# tft_jig.net
KiCad netlist of a schematic drawn in EAGLE
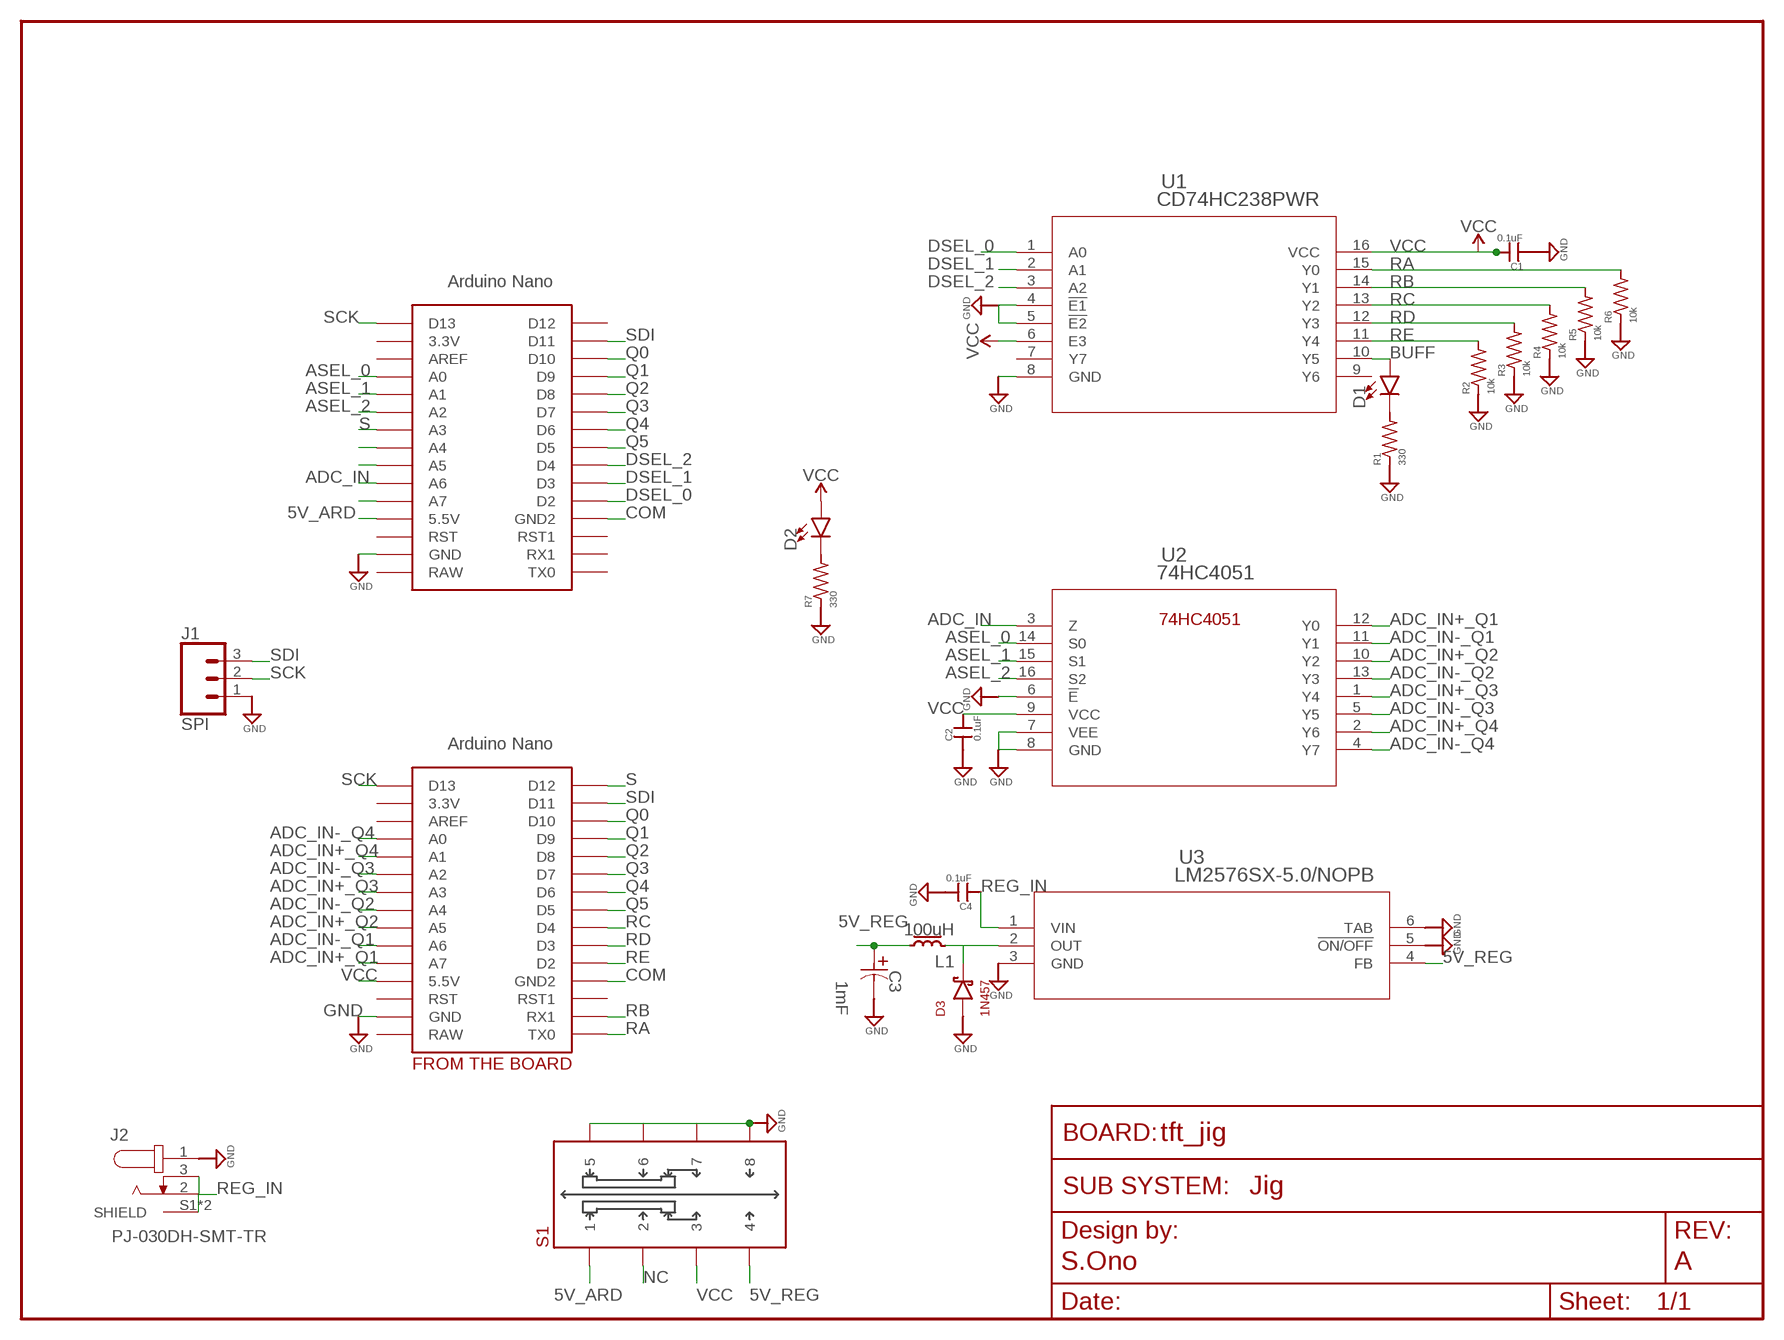
[diagram p0: schematic, sheet 1]

(export (version "E")
  (design (tool "Eeschema 10.0.6"))
  (components
    (comp (ref "C1")
      (value "0.1uF")
      (footprint "eagle-import:0603-CAP")
      (libsource (lib "eagle-import") (part "CAP0603-CAP"))
    )
    (comp (ref "C2")
      (value "0.1uF")
      (footprint "eagle-import:0603-CAP")
      (libsource (lib "eagle-import") (part "CAP0603-CAP"))
    )
    (comp (ref "C3")
      (value "1mF")
      (footprint "eagle-import:PCAP_8X10-ELECT")
      (fields (field (name "MANUFACTURER_PART_NUMBER") "UWT0J102MNL1GS"))
      (libsource (lib "eagle-import") (part "UWT0J102MNL1GS"))
    )
    (comp (ref "C4")
      (value "0.1uF")
      (footprint "eagle-import:0603-CAP")
      (libsource (lib "eagle-import") (part "CAP0603-CAP"))
    )
    (comp (ref "D1")
      (value "LED0603")
      (footprint "eagle-import:LED-0603")
      (libsource (lib "eagle-import") (part "LED0603"))
    )
    (comp (ref "D2")
      (value "LED0603")
      (footprint "eagle-import:LED-0603")
      (libsource (lib "eagle-import") (part "LED0603"))
    )
    (comp (ref "D3")
      (value "1N457")
      (footprint "eagle-import:DIODE_THRU")
      (libsource (lib "eagle-import") (part "1N457"))
    )
    (comp (ref "J1")
      (value "SPI")
      (footprint "eagle-import:1X03")
      (libsource (lib "eagle-import") (part "CONN_03"))
    )
    (comp (ref "J2")
      (value "PJ-030DH-SMT-TR")
      (footprint "eagle-import:CUI_PJ-030DH-SMT-TR")
      (fields (field (name "DIGI-KEY_PART_NUMBER") "CP-030DHPJ-CT-ND") (field (name "MF") "CUI Inc."))
      (libsource (lib "eagle-import") (part "PJ-030DH-SMT-TR"))
    )
    (comp (ref "L1")
      (value "100uH")
      (footprint "eagle-import:IND_2012")
      (fields (field (name "MANUFACTURER_PART_NUMBER") "MLZ2012M1R0HT000"))
      (libsource (lib "eagle-import") (part "IND"))
    )
    (comp (ref "R1")
      (value "330")
      (footprint "eagle-import:R0603")
      (fields (field (name "MANUFACTURER") "Rohm Semiconductor"))
      (libsource (lib "eagle-import") (part "R-US_R0603"))
    )
    (comp (ref "R2")
      (value "10k")
      (footprint "eagle-import:R0603")
      (fields (field (name "MANUFACTURER") "Rohm Semiconductor"))
      (libsource (lib "eagle-import") (part "R-US_R0603"))
    )
    (comp (ref "R3")
      (value "10k")
      (footprint "eagle-import:R0603")
      (fields (field (name "MANUFACTURER") "Rohm Semiconductor"))
      (libsource (lib "eagle-import") (part "R-US_R0603"))
    )
    (comp (ref "R4")
      (value "10k")
      (footprint "eagle-import:R0603")
      (fields (field (name "MANUFACTURER") "Rohm Semiconductor"))
      (libsource (lib "eagle-import") (part "R-US_R0603"))
    )
    (comp (ref "R5")
      (value "10k")
      (footprint "eagle-import:R0603")
      (fields (field (name "MANUFACTURER") "Rohm Semiconductor"))
      (libsource (lib "eagle-import") (part "R-US_R0603"))
    )
    (comp (ref "R6")
      (value "10k")
      (footprint "eagle-import:R0603")
      (fields (field (name "MANUFACTURER") "Rohm Semiconductor"))
      (libsource (lib "eagle-import") (part "R-US_R0603"))
    )
    (comp (ref "R7")
      (value "330")
      (footprint "eagle-import:R0603")
      (fields (field (name "MANUFACTURER") "Rohm Semiconductor"))
      (libsource (lib "eagle-import") (part "R-US_R0603"))
    )
    (comp (ref "S1")
      (value "DP3T")
      (footprint "eagle-import:DP3T")
      (libsource (lib "eagle-import") (part "DP3T"))
    )
    (comp (ref "U$1")
      (value "NANO")
      (footprint "eagle-import:NANO")
      (libsource (lib "eagle-import") (part "NANO"))
    )
    (comp (ref "U$2")
      (value "NANO")
      (footprint "eagle-import:NANO")
      (libsource (lib "eagle-import") (part "NANO"))
    )
    (comp (ref "U1")
      (value "CD74HC238PWR")
      (footprint "eagle-import:PW16")
      (libsource (lib "eagle-import") (part "CD74HC238PWR"))
    )
    (comp (ref "U2")
      (value "74HC4051")
      (footprint "eagle-import:PW16")
      (libsource (lib "eagle-import") (part "74HC4051"))
    )
    (comp (ref "U3")
      (value "LM2576SX-5.0/NOPB")
      (footprint "eagle-import:TS5B")
      (fields (field (name "MANUFACTURER_PART_NUMBER") "LM2576SX5.0NOPB"))
      (libsource (lib "eagle-import") (part "LM2576SX-5.0/NOPB"))
    )
  )
  (nets
    (net (code "1") (name "/5V_ARD") (class "Default")
      (node (ref "S1") (pin "1") (pinfunction "1_1") (pintype "bidirectional"))
      (node (ref "U$1") (pin "5V") (pinfunction "5.5V_5V") (pintype "bidirectional"))
    )
    (net (code "2") (name "/5V_REG") (class "Default")
      (node (ref "C3") (pin "1") (pinfunction "1_1") (pintype "passive"))
      (node (ref "L1") (pin "1") (pinfunction "P$1_1") (pintype "passive"))
      (node (ref "S1") (pin "4") (pinfunction "4_4") (pintype "bidirectional"))
      (node (ref "U3") (pin "4") (pinfunction "FB_4") (pintype "input"))
    )
    (net (code "3") (name "/ADC_IN") (class "Default")
      (node (ref "U$1") (pin "A6") (pinfunction "A6_A6") (pintype "bidirectional"))
      (node (ref "U2") (pin "3") (pinfunction "Z_3") (pintype "input"))
    )
    (net (code "4") (name "/ADC_IN+_Q1") (class "Default")
      (node (ref "U$2") (pin "A7") (pinfunction "A7_A7") (pintype "bidirectional"))
      (node (ref "U2") (pin "12") (pinfunction "Y0_12") (pintype "output"))
    )
    (net (code "5") (name "/ADC_IN+_Q2") (class "Default")
      (node (ref "U$2") (pin "A5") (pinfunction "A5_A5") (pintype "bidirectional"))
      (node (ref "U2") (pin "10") (pinfunction "Y2_10") (pintype "output"))
    )
    (net (code "6") (name "/ADC_IN+_Q3") (class "Default")
      (node (ref "U$2") (pin "A3") (pinfunction "A3_A3") (pintype "bidirectional"))
      (node (ref "U2") (pin "1") (pinfunction "Y4_1") (pintype "output"))
    )
    (net (code "7") (name "/ADC_IN+_Q4") (class "Default")
      (node (ref "U$2") (pin "A1") (pinfunction "A1_A1") (pintype "bidirectional"))
      (node (ref "U2") (pin "2") (pinfunction "Y6_2") (pintype "output"))
    )
    (net (code "8") (name "/ADC_IN-_Q1") (class "Default")
      (node (ref "U$2") (pin "A6") (pinfunction "A6_A6") (pintype "bidirectional"))
      (node (ref "U2") (pin "11") (pinfunction "Y1_11") (pintype "output"))
    )
    (net (code "9") (name "/ADC_IN-_Q2") (class "Default")
      (node (ref "U$2") (pin "A4") (pinfunction "A4_A4") (pintype "bidirectional"))
      (node (ref "U2") (pin "13") (pinfunction "Y3_13") (pintype "output"))
    )
    (net (code "10") (name "/ADC_IN-_Q3") (class "Default")
      (node (ref "U$2") (pin "A2") (pinfunction "A2_A2") (pintype "bidirectional"))
      (node (ref "U2") (pin "5") (pinfunction "Y5_5") (pintype "output"))
    )
    (net (code "11") (name "/ADC_IN-_Q4") (class "Default")
      (node (ref "U$2") (pin "A0") (pinfunction "A0_A0") (pintype "bidirectional"))
      (node (ref "U2") (pin "4") (pinfunction "Y7_4") (pintype "output"))
    )
    (net (code "12") (name "/ASEL_0") (class "Default")
      (node (ref "U$1") (pin "A0") (pinfunction "A0_A0") (pintype "bidirectional"))
      (node (ref "U2") (pin "14") (pinfunction "S0_14") (pintype "input"))
    )
    (net (code "13") (name "/ASEL_1") (class "Default")
      (node (ref "U$1") (pin "A1") (pinfunction "A1_A1") (pintype "bidirectional"))
      (node (ref "U2") (pin "15") (pinfunction "S1_15") (pintype "input"))
    )
    (net (code "14") (name "/ASEL_2") (class "Default")
      (node (ref "U$1") (pin "A2") (pinfunction "A2_A2") (pintype "bidirectional"))
      (node (ref "U2") (pin "16") (pinfunction "S2_16") (pintype "input"))
    )
    (net (code "15") (name "/BUFF") (class "Default")
      (node (ref "D1") (pin "A") (pinfunction "A_A") (pintype "passive"))
      (node (ref "U1") (pin "10") (pinfunction "Y5_10") (pintype "output"))
    )
    (net (code "16") (name "/COM") (class "Default")
      (node (ref "U$1") (pin "GND1") (pinfunction "GND2_GND1") (pintype "bidirectional"))
      (node (ref "U$2") (pin "GND1") (pinfunction "GND2_GND1") (pintype "bidirectional"))
    )
    (net (code "17") (name "/DSEL_0") (class "Default")
      (node (ref "U$1") (pin "D2") (pinfunction "D2_D2") (pintype "bidirectional"))
      (node (ref "U1") (pin "1") (pinfunction "A0_1") (pintype "input"))
    )
    (net (code "18") (name "/DSEL_1") (class "Default")
      (node (ref "U$1") (pin "D3") (pinfunction "D3_D3") (pintype "bidirectional"))
      (node (ref "U1") (pin "2") (pinfunction "A1_2") (pintype "input"))
    )
    (net (code "19") (name "/DSEL_2") (class "Default")
      (node (ref "U$1") (pin "D4") (pinfunction "D4_D4") (pintype "bidirectional"))
      (node (ref "U1") (pin "3") (pinfunction "A2_3") (pintype "input"))
    )
    (net (code "20") (name "/NC") (class "Default")
      (node (ref "S1") (pin "2") (pinfunction "2_2") (pintype "bidirectional"))
    )
    (net (code "21") (name "/Q0") (class "Default")
      (node (ref "U$1") (pin "D10") (pinfunction "D10_D10") (pintype "bidirectional"))
      (node (ref "U$2") (pin "D10") (pinfunction "D10_D10") (pintype "bidirectional"))
    )
    (net (code "22") (name "/Q1") (class "Default")
      (node (ref "U$1") (pin "D9") (pinfunction "D9_D9") (pintype "bidirectional"))
      (node (ref "U$2") (pin "D9") (pinfunction "D9_D9") (pintype "bidirectional"))
    )
    (net (code "23") (name "/Q2") (class "Default")
      (node (ref "U$1") (pin "D8") (pinfunction "D8_D8") (pintype "bidirectional"))
      (node (ref "U$2") (pin "D8") (pinfunction "D8_D8") (pintype "bidirectional"))
    )
    (net (code "24") (name "/Q3") (class "Default")
      (node (ref "U$1") (pin "D7") (pinfunction "D7_D7") (pintype "bidirectional"))
      (node (ref "U$2") (pin "D7") (pinfunction "D7_D7") (pintype "bidirectional"))
    )
    (net (code "25") (name "/Q4") (class "Default")
      (node (ref "U$1") (pin "D6") (pinfunction "D6_D6") (pintype "bidirectional"))
      (node (ref "U$2") (pin "D6") (pinfunction "D6_D6") (pintype "bidirectional"))
    )
    (net (code "26") (name "/Q5") (class "Default")
      (node (ref "U$1") (pin "D5") (pinfunction "D5_D5") (pintype "bidirectional"))
      (node (ref "U$2") (pin "D5") (pinfunction "D5_D5") (pintype "bidirectional"))
    )
    (net (code "27") (name "/RA") (class "Default")
      (node (ref "R6") (pin "2") (pinfunction "2_2") (pintype "passive"))
      (node (ref "U$2") (pin "TX0") (pinfunction "TX0_TX0") (pintype "bidirectional"))
      (node (ref "U1") (pin "15") (pinfunction "Y0_15") (pintype "output"))
    )
    (net (code "28") (name "/RB") (class "Default")
      (node (ref "R5") (pin "2") (pinfunction "2_2") (pintype "passive"))
      (node (ref "U$2") (pin "RX1") (pinfunction "RX1_RX1") (pintype "bidirectional"))
      (node (ref "U1") (pin "14") (pinfunction "Y1_14") (pintype "output"))
    )
    (net (code "29") (name "/RC") (class "Default")
      (node (ref "R4") (pin "2") (pinfunction "2_2") (pintype "passive"))
      (node (ref "U$2") (pin "D4") (pinfunction "D4_D4") (pintype "bidirectional"))
      (node (ref "U1") (pin "13") (pinfunction "Y2_13") (pintype "output"))
    )
    (net (code "30") (name "/RD") (class "Default")
      (node (ref "R3") (pin "2") (pinfunction "2_2") (pintype "passive"))
      (node (ref "U$2") (pin "D3") (pinfunction "D3_D3") (pintype "bidirectional"))
      (node (ref "U1") (pin "12") (pinfunction "Y3_12") (pintype "output"))
    )
    (net (code "31") (name "/RE") (class "Default")
      (node (ref "R2") (pin "2") (pinfunction "2_2") (pintype "passive"))
      (node (ref "U$2") (pin "D2") (pinfunction "D2_D2") (pintype "bidirectional"))
      (node (ref "U1") (pin "11") (pinfunction "Y4_11") (pintype "output"))
    )
    (net (code "32") (name "/REG_IN") (class "Default")
      (node (ref "C4") (pin "1") (pinfunction "1_1") (pintype "passive"))
      (node (ref "J2") (pin "2") (pinfunction "2_2") (pintype "passive"))
      (node (ref "J2") (pin "3") (pinfunction "3_3") (pintype "passive"))
      (node (ref "J2") (pin "S1") (pinfunction "SHIELD_S1") (pintype "passive"))
      (node (ref "J2") (pin "S2") (pinfunction "SHIELD_S2") (pintype "passive"))
      (node (ref "U3") (pin "1") (pinfunction "VIN_1") (pintype "power_in"))
    )
    (net (code "33") (name "/S") (class "Default")
      (node (ref "U$1") (pin "A3") (pinfunction "A3_A3") (pintype "bidirectional"))
      (node (ref "U$2") (pin "D12") (pinfunction "D12_D12") (pintype "bidirectional"))
    )
    (net (code "34") (name "/SCK") (class "Default")
      (node (ref "J1") (pin "2") (pinfunction "2_2") (pintype "passive"))
      (node (ref "U$1") (pin "D13") (pinfunction "D13_D13") (pintype "bidirectional"))
      (node (ref "U$2") (pin "D13") (pinfunction "D13_D13") (pintype "bidirectional"))
    )
    (net (code "35") (name "/SDI") (class "Default")
      (node (ref "J1") (pin "3") (pinfunction "3_3") (pintype "passive"))
      (node (ref "U$1") (pin "D11") (pinfunction "D11_D11") (pintype "bidirectional"))
      (node (ref "U$2") (pin "D11") (pinfunction "D11_D11") (pintype "bidirectional"))
    )
    (net (code "36") (name "GND") (class "Default")
      (node (ref "C1") (pin "1") (pinfunction "1_1") (pintype "passive"))
      (node (ref "C2") (pin "1") (pinfunction "1_1") (pintype "passive"))
      (node (ref "C3") (pin "2") (pinfunction "2_2") (pintype "passive"))
      (node (ref "C4") (pin "2") (pinfunction "2_2") (pintype "passive"))
      (node (ref "D3") (pin "1") (pinfunction "P_1") (pintype "bidirectional"))
      (node (ref "J1") (pin "1") (pinfunction "1_1") (pintype "passive"))
      (node (ref "J2") (pin "1") (pinfunction "1_1") (pintype "passive"))
      (node (ref "R1") (pin "1") (pinfunction "1_1") (pintype "passive"))
      (node (ref "R2") (pin "1") (pinfunction "1_1") (pintype "passive"))
      (node (ref "R3") (pin "1") (pinfunction "1_1") (pintype "passive"))
      (node (ref "R4") (pin "1") (pinfunction "1_1") (pintype "passive"))
      (node (ref "R5") (pin "1") (pinfunction "1_1") (pintype "passive"))
      (node (ref "R6") (pin "1") (pinfunction "1_1") (pintype "passive"))
      (node (ref "R7") (pin "1") (pinfunction "1_1") (pintype "passive"))
      (node (ref "S1") (pin "5") (pinfunction "5_5") (pintype "bidirectional"))
      (node (ref "S1") (pin "6") (pinfunction "6_6") (pintype "bidirectional"))
      (node (ref "S1") (pin "7") (pinfunction "7_7") (pintype "bidirectional"))
      (node (ref "S1") (pin "8") (pinfunction "8_8") (pintype "bidirectional"))
      (node (ref "U$1") (pin "GND") (pinfunction "GND_GND") (pintype "bidirectional"))
      (node (ref "U$2") (pin "GND") (pinfunction "GND_GND") (pintype "bidirectional"))
      (node (ref "U1") (pin "4") (pinfunction "~{E1}_4") (pintype "input"))
      (node (ref "U1") (pin "5") (pinfunction "~{E2}_5") (pintype "input"))
      (node (ref "U1") (pin "8") (pinfunction "GND_8") (pintype "power_in"))
      (node (ref "U2") (pin "6") (pinfunction "~{E}_6") (pintype "input"))
      (node (ref "U2") (pin "7") (pinfunction "VEE_7") (pintype "power_in"))
      (node (ref "U2") (pin "8") (pinfunction "GND_8") (pintype "power_in"))
      (node (ref "U3") (pin "3") (pinfunction "GND_3") (pintype "power_in"))
      (node (ref "U3") (pin "5") (pinfunction "~{ON/OFF}_5") (pintype "input"))
      (node (ref "U3") (pin "6") (pinfunction "TAB_6") (pintype "power_in"))
    )
    (net (code "37") (name "Net-(D1-PadC)") (class "Default")
      (node (ref "D1") (pin "C") (pinfunction "C_C") (pintype "passive"))
      (node (ref "R1") (pin "2") (pinfunction "2_2") (pintype "passive"))
    )
    (net (code "38") (name "Net-(D2-PadC)") (class "Default")
      (node (ref "D2") (pin "C") (pinfunction "C_C") (pintype "passive"))
      (node (ref "R7") (pin "2") (pinfunction "2_2") (pintype "passive"))
    )
    (net (code "39") (name "Net-(D3-N)") (class "Default")
      (node (ref "D3") (pin "2") (pinfunction "N_2") (pintype "bidirectional"))
      (node (ref "L1") (pin "2") (pinfunction "P$2_2") (pintype "passive"))
      (node (ref "U3") (pin "2") (pinfunction "OUT_2") (pintype "power_in"))
    )
    (net (code "40") (name "VCC") (class "Default")
      (node (ref "C1") (pin "2") (pinfunction "2_2") (pintype "passive"))
      (node (ref "C2") (pin "2") (pinfunction "2_2") (pintype "passive"))
      (node (ref "D2") (pin "A") (pinfunction "A_A") (pintype "passive"))
      (node (ref "S1") (pin "3") (pinfunction "3_3") (pintype "bidirectional"))
      (node (ref "U$2") (pin "5V") (pinfunction "5.5V_5V") (pintype "bidirectional"))
      (node (ref "U1") (pin "16") (pinfunction "VCC_16") (pintype "power_in"))
      (node (ref "U1") (pin "6") (pinfunction "E3_6") (pintype "input"))
      (node (ref "U2") (pin "9") (pinfunction "VCC_9") (pintype "power_in"))
    )
    (net (code "41") (name "unconnected-(U$1-Pad3.3V)") (class "Default")
      (node (ref "U$1") (pin "3.3V") (pinfunction "3.3V_3.3V") (pintype "bidirectional"))
    )
    (net (code "42") (name "unconnected-(U$1-PadA4)") (class "Default")
      (node (ref "U$1") (pin "A4") (pinfunction "A4_A4") (pintype "bidirectional"))
    )
    (net (code "43") (name "unconnected-(U$1-PadA5)") (class "Default")
      (node (ref "U$1") (pin "A5") (pinfunction "A5_A5") (pintype "bidirectional"))
    )
    (net (code "44") (name "unconnected-(U$1-PadA7)") (class "Default")
      (node (ref "U$1") (pin "A7") (pinfunction "A7_A7") (pintype "bidirectional"))
    )
    (net (code "45") (name "unconnected-(U$1-PadAREF)") (class "Default")
      (node (ref "U$1") (pin "AREF") (pinfunction "AREF_AREF") (pintype "bidirectional"))
    )
    (net (code "46") (name "unconnected-(U$1-PadD12)") (class "Default")
      (node (ref "U$1") (pin "D12") (pinfunction "D12_D12") (pintype "bidirectional"))
    )
    (net (code "47") (name "unconnected-(U$1-PadRAW)") (class "Default")
      (node (ref "U$1") (pin "RAW") (pinfunction "RAW_RAW") (pintype "bidirectional"))
    )
    (net (code "48") (name "unconnected-(U$1-PadRST)") (class "Default")
      (node (ref "U$1") (pin "RST") (pinfunction "RST_RST") (pintype "bidirectional"))
    )
    (net (code "49") (name "unconnected-(U$1-PadRST1)") (class "Default")
      (node (ref "U$1") (pin "RST1") (pinfunction "RST1_RST1") (pintype "bidirectional"))
    )
    (net (code "50") (name "unconnected-(U$1-PadRX1)") (class "Default")
      (node (ref "U$1") (pin "RX1") (pinfunction "RX1_RX1") (pintype "bidirectional"))
    )
    (net (code "51") (name "unconnected-(U$1-PadTX0)") (class "Default")
      (node (ref "U$1") (pin "TX0") (pinfunction "TX0_TX0") (pintype "bidirectional"))
    )
    (net (code "52") (name "unconnected-(U$2-Pad3.3V)") (class "Default")
      (node (ref "U$2") (pin "3.3V") (pinfunction "3.3V_3.3V") (pintype "bidirectional"))
    )
    (net (code "53") (name "unconnected-(U$2-PadAREF)") (class "Default")
      (node (ref "U$2") (pin "AREF") (pinfunction "AREF_AREF") (pintype "bidirectional"))
    )
    (net (code "54") (name "unconnected-(U$2-PadRAW)") (class "Default")
      (node (ref "U$2") (pin "RAW") (pinfunction "RAW_RAW") (pintype "bidirectional"))
    )
    (net (code "55") (name "unconnected-(U$2-PadRST)") (class "Default")
      (node (ref "U$2") (pin "RST") (pinfunction "RST_RST") (pintype "bidirectional"))
    )
    (net (code "56") (name "unconnected-(U$2-PadRST1)") (class "Default")
      (node (ref "U$2") (pin "RST1") (pinfunction "RST1_RST1") (pintype "bidirectional"))
    )
    (net (code "57") (name "unconnected-(U1-Y6-Pad9)") (class "Default")
      (node (ref "U1") (pin "9") (pinfunction "Y6_9") (pintype "output"))
    )
    (net (code "58") (name "unconnected-(U1-Y7-Pad7)") (class "Default")
      (node (ref "U1") (pin "7") (pinfunction "Y7_7") (pintype "output"))
    )
  )
)
